# pixel-mk-2_0.net
KiCad netlist of a schematic drawn in EAGLE
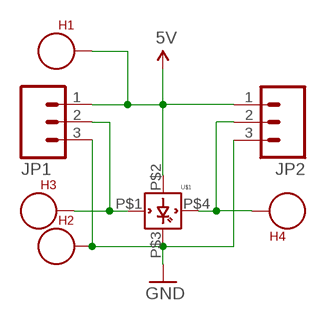
[diagram p0: schematic, sheet 1]

(export (version "E")
  (design (tool "Eeschema 10.0.6"))
  (components
    (comp (ref "H1")
      (value "SEW_HOLE")
      (footprint "eagle-import:SIMPLE_HOLE")
      (libsource (lib "eagle-import") (part "SEW_HOLE"))
    )
    (comp (ref "H2")
      (value "SEW_HOLE")
      (footprint "eagle-import:SIMPLE_HOLE")
      (libsource (lib "eagle-import") (part "SEW_HOLE"))
    )
    (comp (ref "H3")
      (value "SEW_HOLE")
      (footprint "eagle-import:SIMPLE_HOLE")
      (libsource (lib "eagle-import") (part "SEW_HOLE"))
    )
    (comp (ref "H4")
      (value "SEW_HOLE")
      (footprint "eagle-import:SIMPLE_HOLE")
      (libsource (lib "eagle-import") (part "SEW_HOLE"))
    )
    (comp (ref "JP1")
      (value "M03JST-PTH")
      (footprint "eagle-import:JST-3-PTH")
      (libsource (lib "eagle-import") (part "M03JST-PTH"))
    )
    (comp (ref "JP2")
      (value "M03JST-PTH")
      (footprint "eagle-import:JST-3-PTH")
      (libsource (lib "eagle-import") (part "M03JST-PTH"))
    )
    (comp (ref "U$1")
      (value "NEOPIXEL-PTH-5MM-CLEAR")
      (footprint "eagle-import:LED-5MM-PTH-FUCK-RA")
      (libsource (lib "eagle-import") (part "NEOPIXEL-PTH-5MM-CLEAR"))
    )
  )
  (nets
    (net (code "1") (name "5V") (class "Default")
      (node (ref "H1") (pin "P$1") (pinfunction "P$1_P$1") (pintype "bidirectional"))
      (node (ref "JP1") (pin "1") (pinfunction "1_1") (pintype "passive"))
      (node (ref "JP2") (pin "1") (pinfunction "1_1") (pintype "passive"))
      (node (ref "U$1") (pin "P$2") (pinfunction "VDD_P$2") (pintype "bidirectional"))
    )
    (net (code "2") (name "GND") (class "Default")
      (node (ref "H2") (pin "P$1") (pinfunction "P$1_P$1") (pintype "bidirectional"))
      (node (ref "JP1") (pin "3") (pinfunction "3_3") (pintype "passive"))
      (node (ref "JP2") (pin "3") (pinfunction "3_3") (pintype "passive"))
      (node (ref "U$1") (pin "P$3") (pinfunction "GND_P$3") (pintype "bidirectional"))
    )
    (net (code "3") (name "Net-(U$1-DIN)") (class "Default")
      (node (ref "H3") (pin "P$1") (pinfunction "P$1_P$1") (pintype "bidirectional"))
      (node (ref "JP1") (pin "2") (pinfunction "2_2") (pintype "passive"))
      (node (ref "U$1") (pin "P$1") (pinfunction "DIN_P$1") (pintype "input"))
    )
    (net (code "4") (name "Net-(U$1-DOUT)") (class "Default")
      (node (ref "H4") (pin "P$1") (pinfunction "P$1_P$1") (pintype "bidirectional"))
      (node (ref "JP2") (pin "2") (pinfunction "2_2") (pintype "passive"))
      (node (ref "U$1") (pin "P$4") (pinfunction "DOUT_P$4") (pintype "output"))
    )
  )
)
